# eth-ldo.net
KiCad netlist of a schematic drawn in Altium Designer
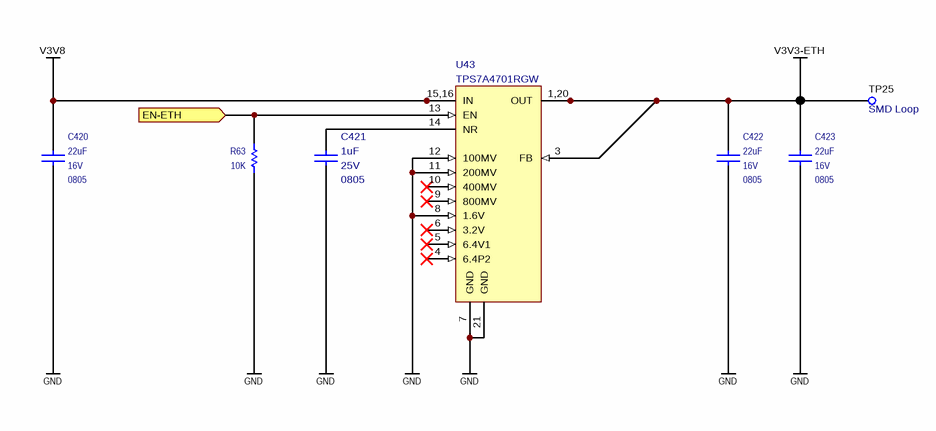
[diagram p0: eth-ldo.SchDoc]

(export (version "E")
  (design (tool "Eeschema 10.0.6"))
  (components
    (comp (ref "C420")
      (value "22uF")
      (footprint "generic:CAPC200X125X145L45N")
      (description "Ceramic Capacitor 22uF ±10% 16V X5R 0805")
      (fields
        (field (name "MANUFACTURER") "Samsung")
        (field (name "VOLTAGE") "16V")
        (field (name "PACKAGE") "0805")
        (field (name "TOLERANCE") "±10%")
      )
      (libsource (lib "generic") (part "CAP 0603"))
    )
    (comp (ref "C421")
      (value "1uF")
      (footprint "CAPC200X125X145L45N")
      (description "Ceramic Capacitor 1uF ±10% 25V X7R 0805")
      (fields
        (field (name "MANUFACTURER") "Taiyo Yuden")
        (field (name "TOLERANCE") "±10%")
        (field (name "PACKAGE") "0805")
        (field (name "VOLTAGE") "25V")
      )
      (libsource (lib "capacitors") (part "CAP"))
    )
    (comp (ref "C422")
      (value "22uF")
      (footprint "generic:CAPC200X125X145L45N")
      (description "Ceramic Capacitor 22uF ±10% 16V X5R 0805")
      (fields
        (field (name "MANUFACTURER") "Samsung")
        (field (name "VOLTAGE") "16V")
        (field (name "PACKAGE") "0805")
        (field (name "TOLERANCE") "±10%")
      )
      (libsource (lib "generic") (part "CAP 0603"))
    )
    (comp (ref "C423")
      (value "22uF")
      (footprint "generic:CAPC200X125X145L45N")
      (description "Ceramic Capacitor 22uF ±10% 16V X5R 0805")
      (fields
        (field (name "MANUFACTURER") "Samsung")
        (field (name "VOLTAGE") "16V")
        (field (name "PACKAGE") "0805")
        (field (name "TOLERANCE") "±10%")
      )
      (libsource (lib "generic") (part "CAP 0603"))
    )
    (comp (ref "R63")
      (value "10K")
      (footprint "RESC1005X40N")
      (description "Thick Film Resistor 10k ±1% 0.1W 50V 0402")
      (fields (field (name "MANUFACTURER") "Panasonic") (field (name "TOLERANCE") "±1%"))
      (libsource (lib "Graviton") (part "RES 0402"))
    )
    (comp (ref "TP25")
      (value "5015")
      (footprint "keystone:5015")
      (description "Test Point SMD")
      (fields (field (name "MANUFACTURER") "Keystone") (field (name "NOTES") "SMD Loop"))
      (libsource (lib "generic") (part "TEST_POINT_SMD_50"))
    )
    (comp (ref "U43")
      (value "TPS7A4701RGW")
      (footprint "QFN65P500X500X100-21N")
      (description "Low-Dropout Linear Regulator 20-VQFN")
      (fields (field (name "MANUFACTURER") "Texas Instruments"))
      (libsource (lib "ti") (part "TPS7A4701RGW_1"))
    )
  )
  (nets
    (net (code "1") (name "/EN-ETH") (class "Default")
      (node (ref "R63") (pin "1") (pinfunction "1_1") (pintype "passive"))
      (node (ref "U43") (pin "13") (pinfunction "EN_13") (pintype "input"))
    )
    (net (code "2") (name "GND") (class "Default")
      (node (ref "C420") (pin "1") (pinfunction "1_1") (pintype "passive"))
      (node (ref "C421") (pin "2") (pinfunction "2_2") (pintype "passive"))
      (node (ref "C422") (pin "1") (pinfunction "1_1") (pintype "passive"))
      (node (ref "C423") (pin "1") (pinfunction "1_1") (pintype "passive"))
      (node (ref "R63") (pin "2") (pinfunction "2_2") (pintype "passive"))
      (node (ref "U43") (pin "11") (pinfunction "200MV_11") (pintype "input"))
      (node (ref "U43") (pin "12") (pinfunction "100MV_12") (pintype "input"))
      (node (ref "U43") (pin "21") (pinfunction "GND_21") (pintype "power_in"))
      (node (ref "U43") (pin "7") (pinfunction "GND_7") (pintype "power_in"))
      (node (ref "U43") (pin "8") (pinfunction "1.6V_8") (pintype "input"))
    )
    (net (code "3") (name "Net-(U43-NR)") (class "Default")
      (node (ref "C421") (pin "1") (pinfunction "1_1") (pintype "passive"))
      (node (ref "U43") (pin "14") (pinfunction "NR_14") (pintype "passive"))
    )
    (net (code "4") (name "V3V3-ETH") (class "Default")
      (node (ref "C422") (pin "2") (pinfunction "2_2") (pintype "passive"))
      (node (ref "C423") (pin "2") (pinfunction "2_2") (pintype "passive"))
      (node (ref "TP25") (pin "1") (pinfunction "1_1") (pintype "passive"))
      (node (ref "U43") (pin "1") (pinfunction "OUT_1") (pintype "passive"))
      (node (ref "U43") (pin "20") (pinfunction "OUT_20") (pintype "passive"))
      (node (ref "U43") (pin "3") (pinfunction "FB_3") (pintype "input"))
    )
    (net (code "5") (name "V3V8") (class "Default")
      (node (ref "C420") (pin "2") (pinfunction "2_2") (pintype "passive"))
      (node (ref "U43") (pin "15") (pinfunction "IN_15") (pintype "passive"))
      (node (ref "U43") (pin "16") (pinfunction "IN_16") (pintype "passive"))
    )
    (net (code "6") (name "unconnected-(U43-3.2V-Pad6)") (class "Default")
      (node (ref "U43") (pin "6") (pinfunction "3.2V_6") (pintype "input+no_connect"))
    )
    (net (code "7") (name "unconnected-(U43-6.4P2-Pad4)") (class "Default")
      (node (ref "U43") (pin "4") (pinfunction "6.4P2_4") (pintype "input+no_connect"))
    )
    (net (code "8") (name "unconnected-(U43-6.4V1-Pad5)") (class "Default")
      (node (ref "U43") (pin "5") (pinfunction "6.4V1_5") (pintype "input+no_connect"))
    )
    (net (code "9") (name "unconnected-(U43-400MV-Pad10)") (class "Default")
      (node (ref "U43") (pin "10") (pinfunction "400MV_10") (pintype "input+no_connect"))
    )
    (net (code "10") (name "unconnected-(U43-800MV-Pad9)") (class "Default")
      (node (ref "U43") (pin "9") (pinfunction "800MV_9") (pintype "input+no_connect"))
    )
  )
)
